# MIDI_Input.net
KiCad netlist of a schematic drawn in EAGLE
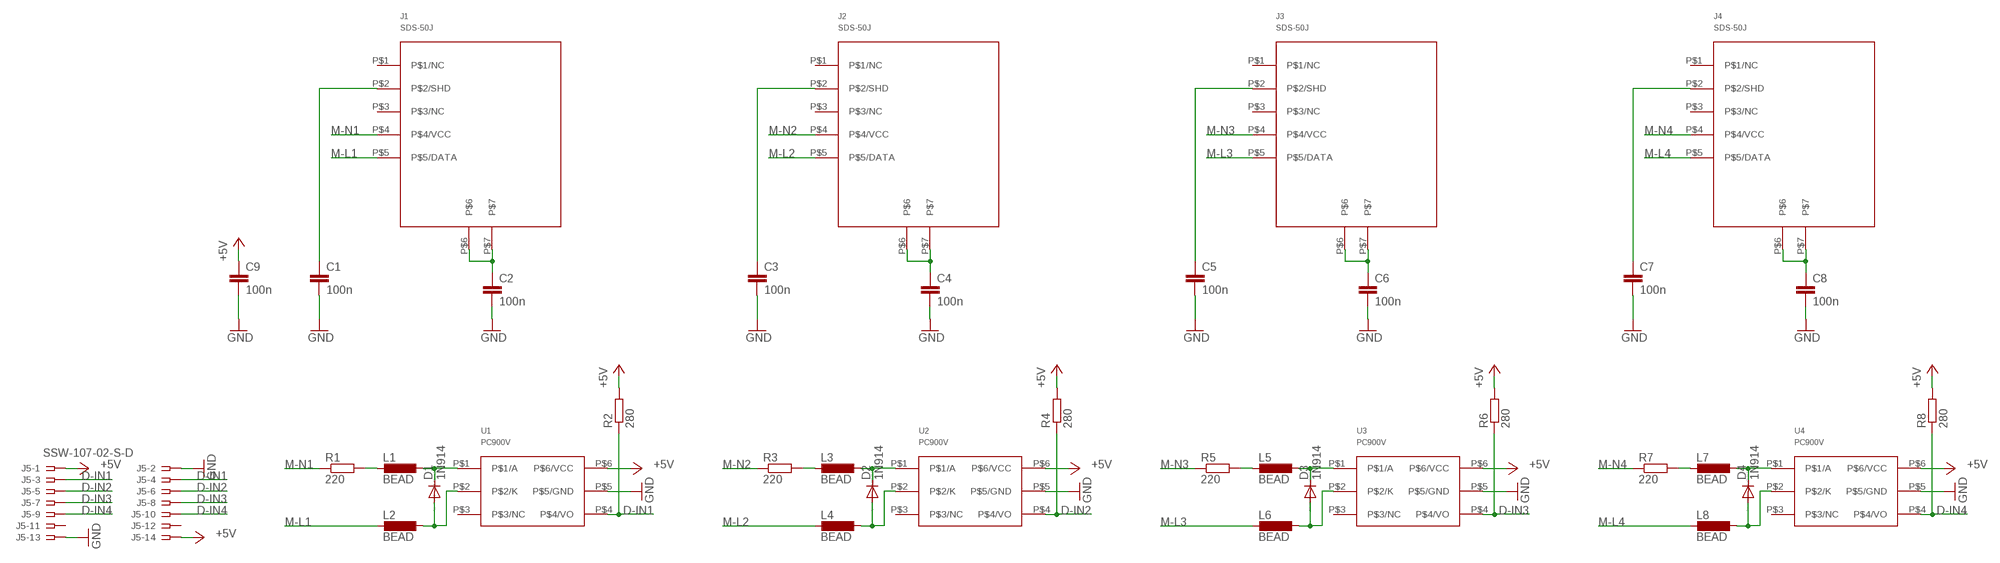
[diagram p0: schematic, sheet 1]

(export (version "E")
  (design (tool "Eeschema 10.0.6"))
  (components
    (comp (ref "C1")
      (value "100n")
      (footprint "eagle-import:C0805")
      (libsource (lib "eagle-import") (part "C-EUC0805"))
    )
    (comp (ref "C2")
      (value "100n")
      (footprint "eagle-import:C0805")
      (libsource (lib "eagle-import") (part "C-EUC0805"))
    )
    (comp (ref "C3")
      (value "100n")
      (footprint "eagle-import:C0805")
      (libsource (lib "eagle-import") (part "C-EUC0805"))
    )
    (comp (ref "C4")
      (value "100n")
      (footprint "eagle-import:C0805")
      (libsource (lib "eagle-import") (part "C-EUC0805"))
    )
    (comp (ref "C5")
      (value "100n")
      (footprint "eagle-import:C0805")
      (libsource (lib "eagle-import") (part "C-EUC0805"))
    )
    (comp (ref "C6")
      (value "100n")
      (footprint "eagle-import:C0805")
      (libsource (lib "eagle-import") (part "C-EUC0805"))
    )
    (comp (ref "C7")
      (value "100n")
      (footprint "eagle-import:C0805")
      (libsource (lib "eagle-import") (part "C-EUC0805"))
    )
    (comp (ref "C8")
      (value "100n")
      (footprint "eagle-import:C0805")
      (libsource (lib "eagle-import") (part "C-EUC0805"))
    )
    (comp (ref "C9")
      (value "100n")
      (footprint "eagle-import:C0805")
      (libsource (lib "eagle-import") (part "C-EUC0805"))
    )
    (comp (ref "D1")
      (value "1N914")
      (footprint "eagle-import:SOD323-W")
      (libsource (lib "eagle-import") (part "1N914"))
    )
    (comp (ref "D2")
      (value "1N914")
      (footprint "eagle-import:SOD323-W")
      (libsource (lib "eagle-import") (part "1N914"))
    )
    (comp (ref "D3")
      (value "1N914")
      (footprint "eagle-import:SOD323-W")
      (libsource (lib "eagle-import") (part "1N914"))
    )
    (comp (ref "D4")
      (value "1N914")
      (footprint "eagle-import:SOD323-W")
      (libsource (lib "eagle-import") (part "1N914"))
    )
    (comp (ref "J1")
      (value "SDS-50J")
      (footprint "eagle-import:SDS-50J")
      (libsource (lib "eagle-import") (part "SDS-50J"))
    )
    (comp (ref "J2")
      (value "SDS-50J")
      (footprint "eagle-import:SDS-50J")
      (libsource (lib "eagle-import") (part "SDS-50J"))
    )
    (comp (ref "J3")
      (value "SDS-50J")
      (footprint "eagle-import:SDS-50J")
      (libsource (lib "eagle-import") (part "SDS-50J"))
    )
    (comp (ref "J4")
      (value "SDS-50J")
      (footprint "eagle-import:SDS-50J")
      (libsource (lib "eagle-import") (part "SDS-50J"))
    )
    (comp (ref "J5")
      (value "SSW-107-02-S-D")
      (footprint "eagle-import:SSW-107-02-S-D")
      (libsource (lib "eagle-import") (part "SSW-107-02-S-D"))
    )
    (comp (ref "L1")
      (value "BEAD")
      (footprint "eagle-import:L0805")
      (libsource (lib "eagle-import") (part "BEAD"))
    )
    (comp (ref "L2")
      (value "BEAD")
      (footprint "eagle-import:L0805")
      (libsource (lib "eagle-import") (part "BEAD"))
    )
    (comp (ref "L3")
      (value "BEAD")
      (footprint "eagle-import:L0805")
      (libsource (lib "eagle-import") (part "BEAD"))
    )
    (comp (ref "L4")
      (value "BEAD")
      (footprint "eagle-import:L0805")
      (libsource (lib "eagle-import") (part "BEAD"))
    )
    (comp (ref "L5")
      (value "BEAD")
      (footprint "eagle-import:L0805")
      (libsource (lib "eagle-import") (part "BEAD"))
    )
    (comp (ref "L6")
      (value "BEAD")
      (footprint "eagle-import:L0805")
      (libsource (lib "eagle-import") (part "BEAD"))
    )
    (comp (ref "L7")
      (value "BEAD")
      (footprint "eagle-import:L0805")
      (libsource (lib "eagle-import") (part "BEAD"))
    )
    (comp (ref "L8")
      (value "BEAD")
      (footprint "eagle-import:L0805")
      (libsource (lib "eagle-import") (part "BEAD"))
    )
    (comp (ref "R1")
      (value "220")
      (footprint "eagle-import:R0805")
      (libsource (lib "eagle-import") (part "R-EU_R0805"))
    )
    (comp (ref "R2")
      (value "280")
      (footprint "eagle-import:R0805")
      (libsource (lib "eagle-import") (part "R-EU_R0805"))
    )
    (comp (ref "R3")
      (value "220")
      (footprint "eagle-import:R0805")
      (libsource (lib "eagle-import") (part "R-EU_R0805"))
    )
    (comp (ref "R4")
      (value "280")
      (footprint "eagle-import:R0805")
      (libsource (lib "eagle-import") (part "R-EU_R0805"))
    )
    (comp (ref "R5")
      (value "220")
      (footprint "eagle-import:R0805")
      (libsource (lib "eagle-import") (part "R-EU_R0805"))
    )
    (comp (ref "R6")
      (value "280")
      (footprint "eagle-import:R0805")
      (libsource (lib "eagle-import") (part "R-EU_R0805"))
    )
    (comp (ref "R7")
      (value "220")
      (footprint "eagle-import:R0805")
      (libsource (lib "eagle-import") (part "R-EU_R0805"))
    )
    (comp (ref "R8")
      (value "280")
      (footprint "eagle-import:R0805")
      (libsource (lib "eagle-import") (part "R-EU_R0805"))
    )
    (comp (ref "U1")
      (value "PC900V")
      (footprint "eagle-import:DIL06")
      (libsource (lib "eagle-import") (part "PC900V"))
    )
    (comp (ref "U2")
      (value "PC900V")
      (footprint "eagle-import:DIL06")
      (libsource (lib "eagle-import") (part "PC900V"))
    )
    (comp (ref "U3")
      (value "PC900V")
      (footprint "eagle-import:DIL06")
      (libsource (lib "eagle-import") (part "PC900V"))
    )
    (comp (ref "U4")
      (value "PC900V")
      (footprint "eagle-import:DIL06")
      (libsource (lib "eagle-import") (part "PC900V"))
    )
  )
  (nets
    (net (code "1") (name "+5V") (class "Default")
      (node (ref "C9") (pin "1") (pinfunction "1_1") (pintype "passive"))
      (node (ref "J5") (pin "1") (pinfunction "1_1") (pintype "passive"))
      (node (ref "J5") (pin "14") (pinfunction "1_14") (pintype "passive"))
      (node (ref "R2") (pin "2") (pinfunction "2_2") (pintype "passive"))
      (node (ref "R4") (pin "2") (pinfunction "2_2") (pintype "passive"))
      (node (ref "R6") (pin "2") (pinfunction "2_2") (pintype "passive"))
      (node (ref "R8") (pin "2") (pinfunction "2_2") (pintype "passive"))
      (node (ref "U1") (pin "P$6") (pinfunction "P$6/VCC_P$6") (pintype "bidirectional"))
      (node (ref "U2") (pin "P$6") (pinfunction "P$6/VCC_P$6") (pintype "bidirectional"))
      (node (ref "U3") (pin "P$6") (pinfunction "P$6/VCC_P$6") (pintype "bidirectional"))
      (node (ref "U4") (pin "P$6") (pinfunction "P$6/VCC_P$6") (pintype "bidirectional"))
    )
    (net (code "2") (name "/D-IN1") (class "Default")
      (node (ref "J5") (pin "3") (pinfunction "1_3") (pintype "passive"))
      (node (ref "J5") (pin "4") (pinfunction "1_4") (pintype "passive"))
      (node (ref "R2") (pin "1") (pinfunction "1_1") (pintype "passive"))
      (node (ref "U1") (pin "P$4") (pinfunction "P$4/VO_P$4") (pintype "bidirectional"))
    )
    (net (code "3") (name "/D-IN2") (class "Default")
      (node (ref "J5") (pin "5") (pinfunction "1_5") (pintype "passive"))
      (node (ref "J5") (pin "6") (pinfunction "1_6") (pintype "passive"))
      (node (ref "R4") (pin "1") (pinfunction "1_1") (pintype "passive"))
      (node (ref "U2") (pin "P$4") (pinfunction "P$4/VO_P$4") (pintype "bidirectional"))
    )
    (net (code "4") (name "/D-IN3") (class "Default")
      (node (ref "J5") (pin "7") (pinfunction "1_7") (pintype "passive"))
      (node (ref "J5") (pin "8") (pinfunction "1_8") (pintype "passive"))
      (node (ref "R6") (pin "1") (pinfunction "1_1") (pintype "passive"))
      (node (ref "U3") (pin "P$4") (pinfunction "P$4/VO_P$4") (pintype "bidirectional"))
    )
    (net (code "5") (name "/D-IN4") (class "Default")
      (node (ref "J5") (pin "10") (pinfunction "1_10") (pintype "passive"))
      (node (ref "J5") (pin "9") (pinfunction "1_9") (pintype "passive"))
      (node (ref "R8") (pin "1") (pinfunction "1_1") (pintype "passive"))
      (node (ref "U4") (pin "P$4") (pinfunction "P$4/VO_P$4") (pintype "bidirectional"))
    )
    (net (code "6") (name "/M-L1") (class "Default")
      (node (ref "J1") (pin "P$5") (pinfunction "P$5/DATA_P$5") (pintype "bidirectional"))
      (node (ref "L2") (pin "1") (pinfunction "1_1") (pintype "passive"))
    )
    (net (code "7") (name "/M-L2") (class "Default")
      (node (ref "J2") (pin "P$5") (pinfunction "P$5/DATA_P$5") (pintype "bidirectional"))
      (node (ref "L4") (pin "1") (pinfunction "1_1") (pintype "passive"))
    )
    (net (code "8") (name "/M-L3") (class "Default")
      (node (ref "J3") (pin "P$5") (pinfunction "P$5/DATA_P$5") (pintype "bidirectional"))
      (node (ref "L6") (pin "1") (pinfunction "1_1") (pintype "passive"))
    )
    (net (code "9") (name "/M-L4") (class "Default")
      (node (ref "J4") (pin "P$5") (pinfunction "P$5/DATA_P$5") (pintype "bidirectional"))
      (node (ref "L8") (pin "1") (pinfunction "1_1") (pintype "passive"))
    )
    (net (code "10") (name "/M-N1") (class "Default")
      (node (ref "J1") (pin "P$4") (pinfunction "P$4/VCC_P$4") (pintype "bidirectional"))
      (node (ref "R1") (pin "1") (pinfunction "1_1") (pintype "passive"))
    )
    (net (code "11") (name "/M-N2") (class "Default")
      (node (ref "J2") (pin "P$4") (pinfunction "P$4/VCC_P$4") (pintype "bidirectional"))
      (node (ref "R3") (pin "1") (pinfunction "1_1") (pintype "passive"))
    )
    (net (code "12") (name "/M-N3") (class "Default")
      (node (ref "J3") (pin "P$4") (pinfunction "P$4/VCC_P$4") (pintype "bidirectional"))
      (node (ref "R5") (pin "1") (pinfunction "1_1") (pintype "passive"))
    )
    (net (code "13") (name "/M-N4") (class "Default")
      (node (ref "J4") (pin "P$4") (pinfunction "P$4/VCC_P$4") (pintype "bidirectional"))
      (node (ref "R7") (pin "1") (pinfunction "1_1") (pintype "passive"))
    )
    (net (code "14") (name "GND") (class "Default")
      (node (ref "C1") (pin "2") (pinfunction "2_2") (pintype "passive"))
      (node (ref "C2") (pin "2") (pinfunction "2_2") (pintype "passive"))
      (node (ref "C3") (pin "2") (pinfunction "2_2") (pintype "passive"))
      (node (ref "C4") (pin "2") (pinfunction "2_2") (pintype "passive"))
      (node (ref "C5") (pin "2") (pinfunction "2_2") (pintype "passive"))
      (node (ref "C6") (pin "2") (pinfunction "2_2") (pintype "passive"))
      (node (ref "C7") (pin "2") (pinfunction "2_2") (pintype "passive"))
      (node (ref "C8") (pin "2") (pinfunction "2_2") (pintype "passive"))
      (node (ref "C9") (pin "2") (pinfunction "2_2") (pintype "passive"))
      (node (ref "J5") (pin "13") (pinfunction "1_13") (pintype "passive"))
      (node (ref "J5") (pin "2") (pinfunction "1_2") (pintype "passive"))
      (node (ref "U1") (pin "P$5") (pinfunction "P$5/GND_P$5") (pintype "bidirectional"))
      (node (ref "U2") (pin "P$5") (pinfunction "P$5/GND_P$5") (pintype "bidirectional"))
      (node (ref "U3") (pin "P$5") (pinfunction "P$5/GND_P$5") (pintype "bidirectional"))
      (node (ref "U4") (pin "P$5") (pinfunction "P$5/GND_P$5") (pintype "bidirectional"))
    )
    (net (code "15") (name "Net-(C2-Pad1)") (class "Default")
      (node (ref "C2") (pin "1") (pinfunction "1_1") (pintype "passive"))
      (node (ref "J1") (pin "P$6") (pinfunction "P$6_P$6") (pintype "bidirectional"))
      (node (ref "J1") (pin "P$7") (pinfunction "P$7_P$7") (pintype "bidirectional"))
    )
    (net (code "16") (name "Net-(C4-Pad1)") (class "Default")
      (node (ref "C4") (pin "1") (pinfunction "1_1") (pintype "passive"))
      (node (ref "J2") (pin "P$6") (pinfunction "P$6_P$6") (pintype "bidirectional"))
      (node (ref "J2") (pin "P$7") (pinfunction "P$7_P$7") (pintype "bidirectional"))
    )
    (net (code "17") (name "Net-(C6-Pad1)") (class "Default")
      (node (ref "C6") (pin "1") (pinfunction "1_1") (pintype "passive"))
      (node (ref "J3") (pin "P$6") (pinfunction "P$6_P$6") (pintype "bidirectional"))
      (node (ref "J3") (pin "P$7") (pinfunction "P$7_P$7") (pintype "bidirectional"))
    )
    (net (code "18") (name "Net-(C8-Pad1)") (class "Default")
      (node (ref "C8") (pin "1") (pinfunction "1_1") (pintype "passive"))
      (node (ref "J4") (pin "P$6") (pinfunction "P$6_P$6") (pintype "bidirectional"))
      (node (ref "J4") (pin "P$7") (pinfunction "P$7_P$7") (pintype "bidirectional"))
    )
    (net (code "19") (name "Net-(J1-P$2{slash}SHD)") (class "Default")
      (node (ref "C1") (pin "1") (pinfunction "1_1") (pintype "passive"))
      (node (ref "J1") (pin "P$2") (pinfunction "P$2/SHD_P$2") (pintype "bidirectional"))
    )
    (net (code "20") (name "Net-(J2-P$2{slash}SHD)") (class "Default")
      (node (ref "C3") (pin "1") (pinfunction "1_1") (pintype "passive"))
      (node (ref "J2") (pin "P$2") (pinfunction "P$2/SHD_P$2") (pintype "bidirectional"))
    )
    (net (code "21") (name "Net-(J3-P$2{slash}SHD)") (class "Default")
      (node (ref "C5") (pin "1") (pinfunction "1_1") (pintype "passive"))
      (node (ref "J3") (pin "P$2") (pinfunction "P$2/SHD_P$2") (pintype "bidirectional"))
    )
    (net (code "22") (name "Net-(J4-P$2{slash}SHD)") (class "Default")
      (node (ref "C7") (pin "1") (pinfunction "1_1") (pintype "passive"))
      (node (ref "J4") (pin "P$2") (pinfunction "P$2/SHD_P$2") (pintype "bidirectional"))
    )
    (net (code "23") (name "Net-(L1-Pad1)") (class "Default")
      (node (ref "L1") (pin "1") (pinfunction "1_1") (pintype "passive"))
      (node (ref "R1") (pin "2") (pinfunction "2_2") (pintype "passive"))
    )
    (net (code "24") (name "Net-(L3-Pad1)") (class "Default")
      (node (ref "L3") (pin "1") (pinfunction "1_1") (pintype "passive"))
      (node (ref "R3") (pin "2") (pinfunction "2_2") (pintype "passive"))
    )
    (net (code "25") (name "Net-(L5-Pad1)") (class "Default")
      (node (ref "L5") (pin "1") (pinfunction "1_1") (pintype "passive"))
      (node (ref "R5") (pin "2") (pinfunction "2_2") (pintype "passive"))
    )
    (net (code "26") (name "Net-(L7-Pad1)") (class "Default")
      (node (ref "L7") (pin "1") (pinfunction "1_1") (pintype "passive"))
      (node (ref "R7") (pin "2") (pinfunction "2_2") (pintype "passive"))
    )
    (net (code "27") (name "Net-(U1-P$1{slash}A)") (class "Default")
      (node (ref "D1") (pin "C") (pinfunction "C_C") (pintype "passive"))
      (node (ref "L1") (pin "2") (pinfunction "2_2") (pintype "passive"))
      (node (ref "U1") (pin "P$1") (pinfunction "P$1/A_P$1") (pintype "bidirectional"))
    )
    (net (code "28") (name "Net-(U1-P$2{slash}K)") (class "Default")
      (node (ref "D1") (pin "A") (pinfunction "A_A") (pintype "passive"))
      (node (ref "L2") (pin "2") (pinfunction "2_2") (pintype "passive"))
      (node (ref "U1") (pin "P$2") (pinfunction "P$2/K_P$2") (pintype "bidirectional"))
    )
    (net (code "29") (name "Net-(U2-P$1{slash}A)") (class "Default")
      (node (ref "D2") (pin "C") (pinfunction "C_C") (pintype "passive"))
      (node (ref "L3") (pin "2") (pinfunction "2_2") (pintype "passive"))
      (node (ref "U2") (pin "P$1") (pinfunction "P$1/A_P$1") (pintype "bidirectional"))
    )
    (net (code "30") (name "Net-(U2-P$2{slash}K)") (class "Default")
      (node (ref "D2") (pin "A") (pinfunction "A_A") (pintype "passive"))
      (node (ref "L4") (pin "2") (pinfunction "2_2") (pintype "passive"))
      (node (ref "U2") (pin "P$2") (pinfunction "P$2/K_P$2") (pintype "bidirectional"))
    )
    (net (code "31") (name "Net-(U3-P$1{slash}A)") (class "Default")
      (node (ref "D3") (pin "C") (pinfunction "C_C") (pintype "passive"))
      (node (ref "L5") (pin "2") (pinfunction "2_2") (pintype "passive"))
      (node (ref "U3") (pin "P$1") (pinfunction "P$1/A_P$1") (pintype "bidirectional"))
    )
    (net (code "32") (name "Net-(U3-P$2{slash}K)") (class "Default")
      (node (ref "D3") (pin "A") (pinfunction "A_A") (pintype "passive"))
      (node (ref "L6") (pin "2") (pinfunction "2_2") (pintype "passive"))
      (node (ref "U3") (pin "P$2") (pinfunction "P$2/K_P$2") (pintype "bidirectional"))
    )
    (net (code "33") (name "Net-(U4-P$1{slash}A)") (class "Default")
      (node (ref "D4") (pin "C") (pinfunction "C_C") (pintype "passive"))
      (node (ref "L7") (pin "2") (pinfunction "2_2") (pintype "passive"))
      (node (ref "U4") (pin "P$1") (pinfunction "P$1/A_P$1") (pintype "bidirectional"))
    )
    (net (code "34") (name "Net-(U4-P$2{slash}K)") (class "Default")
      (node (ref "D4") (pin "A") (pinfunction "A_A") (pintype "passive"))
      (node (ref "L8") (pin "2") (pinfunction "2_2") (pintype "passive"))
      (node (ref "U4") (pin "P$2") (pinfunction "P$2/K_P$2") (pintype "bidirectional"))
    )
    (net (code "35") (name "unconnected-(J1-P$1{slash}NC-PadP$1)") (class "Default")
      (node (ref "J1") (pin "P$1") (pinfunction "P$1/NC_P$1") (pintype "bidirectional"))
    )
    (net (code "36") (name "unconnected-(J1-P$3{slash}NC-PadP$3)") (class "Default")
      (node (ref "J1") (pin "P$3") (pinfunction "P$3/NC_P$3") (pintype "bidirectional"))
    )
    (net (code "37") (name "unconnected-(J2-P$1{slash}NC-PadP$1)") (class "Default")
      (node (ref "J2") (pin "P$1") (pinfunction "P$1/NC_P$1") (pintype "bidirectional"))
    )
    (net (code "38") (name "unconnected-(J2-P$3{slash}NC-PadP$3)") (class "Default")
      (node (ref "J2") (pin "P$3") (pinfunction "P$3/NC_P$3") (pintype "bidirectional"))
    )
    (net (code "39") (name "unconnected-(J3-P$1{slash}NC-PadP$1)") (class "Default")
      (node (ref "J3") (pin "P$1") (pinfunction "P$1/NC_P$1") (pintype "bidirectional"))
    )
    (net (code "40") (name "unconnected-(J3-P$3{slash}NC-PadP$3)") (class "Default")
      (node (ref "J3") (pin "P$3") (pinfunction "P$3/NC_P$3") (pintype "bidirectional"))
    )
    (net (code "41") (name "unconnected-(J4-P$1{slash}NC-PadP$1)") (class "Default")
      (node (ref "J4") (pin "P$1") (pinfunction "P$1/NC_P$1") (pintype "bidirectional"))
    )
    (net (code "42") (name "unconnected-(J4-P$3{slash}NC-PadP$3)") (class "Default")
      (node (ref "J4") (pin "P$3") (pinfunction "P$3/NC_P$3") (pintype "bidirectional"))
    )
    (net (code "43") (name "unconnected-(J5C-1-Pad11)") (class "Default")
      (node (ref "J5") (pin "11") (pinfunction "1_11") (pintype "passive"))
    )
    (net (code "44") (name "unconnected-(J5D-1-Pad12)") (class "Default")
      (node (ref "J5") (pin "12") (pinfunction "1_12") (pintype "passive"))
    )
    (net (code "45") (name "unconnected-(U1-P$3{slash}NC-PadP$3)") (class "Default")
      (node (ref "U1") (pin "P$3") (pinfunction "P$3/NC_P$3") (pintype "bidirectional"))
    )
    (net (code "46") (name "unconnected-(U2-P$3{slash}NC-PadP$3)") (class "Default")
      (node (ref "U2") (pin "P$3") (pinfunction "P$3/NC_P$3") (pintype "bidirectional"))
    )
    (net (code "47") (name "unconnected-(U3-P$3{slash}NC-PadP$3)") (class "Default")
      (node (ref "U3") (pin "P$3") (pinfunction "P$3/NC_P$3") (pintype "bidirectional"))
    )
    (net (code "48") (name "unconnected-(U4-P$3{slash}NC-PadP$3)") (class "Default")
      (node (ref "U4") (pin "P$3") (pinfunction "P$3/NC_P$3") (pintype "bidirectional"))
    )
  )
)
